# LPCB235_-_HEC1-4.net
KiCad netlist of a schematic drawn in Altium Designer
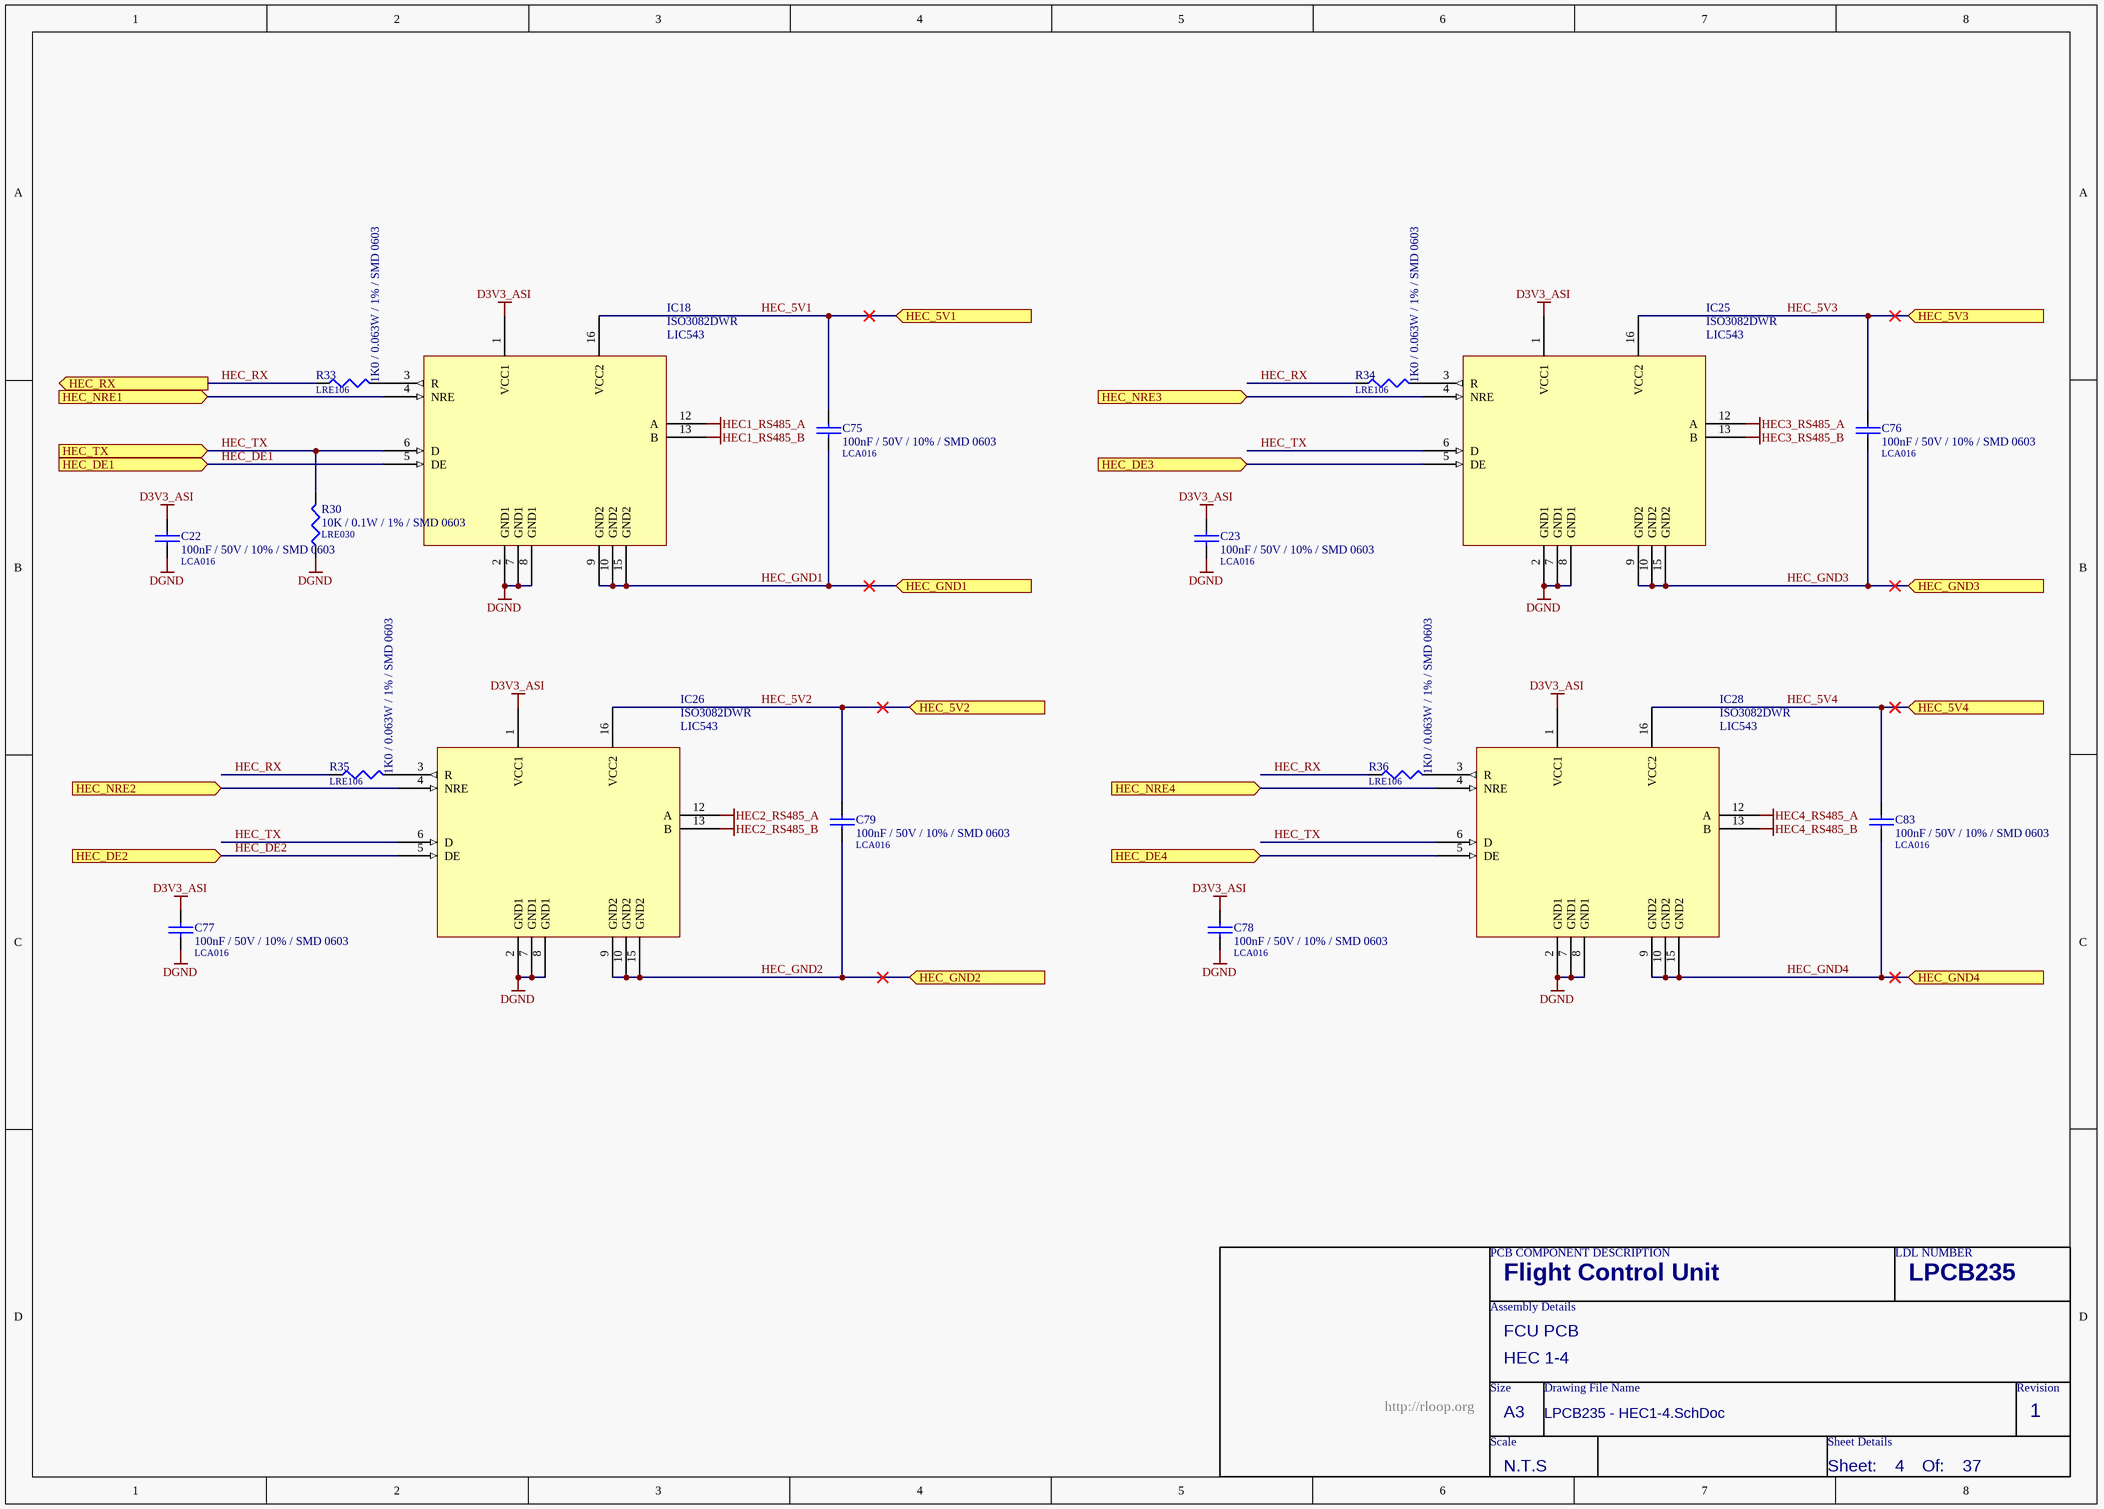
[diagram p0: LPCB235 - HEC1-4.SchDoc]

(export (version "E")
  (design (tool "Eeschema 10.0.6"))
  (components
    (comp (ref "C22")
      (value "100nF / 50V / 10% / SMD 0603")
      (footprint "LFP011__CC1608-0603-IPC7351_B")
      (description "Capacitor, Ceramic Chip, 100nF (0.1uF), 50V, 5%, SMD 0603 [LCA016]")
      (fields (field (name "LDL_NUMBER") "LCA016"))
      (libsource (lib "LDL_Capacitors") (part "100nF / 50V / 10% / SMD 0603"))
    )
    (comp (ref "C23")
      (value "100nF / 50V / 10% / SMD 0603")
      (footprint "LFP011__CC1608-0603-IPC7351_B")
      (description "Capacitor, Ceramic Chip, 100nF (0.1uF), 50V, 5%, SMD 0603 [LCA016]")
      (fields (field (name "LDL_NUMBER") "LCA016"))
      (libsource (lib "LDL_Capacitors") (part "100nF / 50V / 10% / SMD 0603"))
    )
    (comp (ref "C75")
      (value "100nF / 50V / 10% / SMD 0603")
      (footprint "LFP011__CC1608-0603-IPC7351_B")
      (description "Capacitor, Ceramic Chip, 100nF (0.1uF), 50V, 5%, SMD 0603 [LCA016]")
      (fields (field (name "LDL_NUMBER") "LCA016"))
      (libsource (lib "LDL_Capacitors") (part "100nF / 50V / 10% / SMD 0603"))
    )
    (comp (ref "C76")
      (value "100nF / 50V / 10% / SMD 0603")
      (footprint "LFP011__CC1608-0603-IPC7351_B")
      (description "Capacitor, Ceramic Chip, 100nF (0.1uF), 50V, 5%, SMD 0603 [LCA016]")
      (fields (field (name "LDL_NUMBER") "LCA016"))
      (libsource (lib "LDL_Capacitors") (part "100nF / 50V / 10% / SMD 0603"))
    )
    (comp (ref "C77")
      (value "100nF / 50V / 10% / SMD 0603")
      (footprint "LFP011__CC1608-0603-IPC7351_B")
      (description "Capacitor, Ceramic Chip, 100nF (0.1uF), 50V, 5%, SMD 0603 [LCA016]")
      (fields (field (name "LDL_NUMBER") "LCA016"))
      (libsource (lib "LDL_Capacitors") (part "100nF / 50V / 10% / SMD 0603"))
    )
    (comp (ref "C78")
      (value "100nF / 50V / 10% / SMD 0603")
      (footprint "LFP011__CC1608-0603-IPC7351_B")
      (description "Capacitor, Ceramic Chip, 100nF (0.1uF), 50V, 5%, SMD 0603 [LCA016]")
      (fields (field (name "LDL_NUMBER") "LCA016"))
      (libsource (lib "LDL_Capacitors") (part "100nF / 50V / 10% / SMD 0603"))
    )
    (comp (ref "C79")
      (value "100nF / 50V / 10% / SMD 0603")
      (footprint "LFP011__CC1608-0603-IPC7351_B")
      (description "Capacitor, Ceramic Chip, 100nF (0.1uF), 50V, 5%, SMD 0603 [LCA016]")
      (fields (field (name "LDL_NUMBER") "LCA016"))
      (libsource (lib "LDL_Capacitors") (part "100nF / 50V / 10% / SMD 0603"))
    )
    (comp (ref "C83")
      (value "100nF / 50V / 10% / SMD 0603")
      (footprint "LFP011__CC1608-0603-IPC7351_B")
      (description "Capacitor, Ceramic Chip, 100nF (0.1uF), 50V, 5%, SMD 0603 [LCA016]")
      (fields (field (name "LDL_NUMBER") "LCA016"))
      (libsource (lib "LDL_Capacitors") (part "100nF / 50V / 10% / SMD 0603"))
    )
    (comp (ref "IC18")
      (value "ISO3082DWR")
      (footprint "LFP068__SO-G16/G6.9")
      (description "IC, RS485 Isolator, SMD SOIC 16 [LIC543]")
      (fields (field (name "LDL_NUMBER") "LIC543"))
      (libsource (lib "LDL_Semiconductors") (part "ISO3082DWR"))
    )
    (comp (ref "IC25")
      (value "ISO3082DWR")
      (footprint "LFP068__SO-G16/G6.9")
      (description "IC, RS485 Isolator, SMD SOIC 16 [LIC543]")
      (fields (field (name "LDL_NUMBER") "LIC543"))
      (libsource (lib "LDL_Semiconductors") (part "ISO3082DWR"))
    )
    (comp (ref "IC26")
      (value "ISO3082DWR")
      (footprint "LFP068__SO-G16/G6.9")
      (description "IC, RS485 Isolator, SMD SOIC 16 [LIC543]")
      (fields (field (name "LDL_NUMBER") "LIC543"))
      (libsource (lib "LDL_Semiconductors") (part "ISO3082DWR"))
    )
    (comp (ref "IC28")
      (value "ISO3082DWR")
      (footprint "LFP068__SO-G16/G6.9")
      (description "IC, RS485 Isolator, SMD SOIC 16 [LIC543]")
      (fields (field (name "LDL_NUMBER") "LIC543"))
      (libsource (lib "LDL_Semiconductors") (part "ISO3082DWR"))
    )
    (comp (ref "R30")
      (value "10K / 0.1W / 1% / SMD 0603")
      (footprint "LFP020__CR1608-0603-IPC7351_B")
      (description "Resistor, Ceramic Chip, 10K, 0.1W, 1%, SMD 0603 [LRE030]")
      (fields (field (name "LDL_NUMBER") "LRE030"))
      (libsource (lib "LDL_Resistors") (part "10K / 0.1W / 1% / SMD 0603"))
    )
    (comp (ref "R33")
      (value "1K0 / 0.063W / 1% / SMD 0603")
      (footprint "LFP020__CR1608-0603-IPC7351_B")
      (description "Resistor, Ceramic Chip, 1K0, 0.063W, 1%, SMD 0603 [LRE106]")
      (fields (field (name "LDL_NUMBER") "LRE106"))
      (libsource (lib "LDL_Resistors") (part "1K0 / 0.063W / 1% / SMD 0603"))
    )
    (comp (ref "R34")
      (value "1K0 / 0.063W / 1% / SMD 0603")
      (footprint "LFP020__CR1608-0603-IPC7351_B")
      (description "Resistor, Ceramic Chip, 1K0, 0.063W, 1%, SMD 0603 [LRE106]")
      (fields (field (name "LDL_NUMBER") "LRE106"))
      (libsource (lib "LDL_Resistors") (part "1K0 / 0.063W / 1% / SMD 0603"))
    )
    (comp (ref "R35")
      (value "1K0 / 0.063W / 1% / SMD 0603")
      (footprint "LFP020__CR1608-0603-IPC7351_B")
      (description "Resistor, Ceramic Chip, 1K0, 0.063W, 1%, SMD 0603 [LRE106]")
      (fields (field (name "LDL_NUMBER") "LRE106"))
      (libsource (lib "LDL_Resistors") (part "1K0 / 0.063W / 1% / SMD 0603"))
    )
    (comp (ref "R36")
      (value "1K0 / 0.063W / 1% / SMD 0603")
      (footprint "LFP020__CR1608-0603-IPC7351_B")
      (description "Resistor, Ceramic Chip, 1K0, 0.063W, 1%, SMD 0603 [LRE106]")
      (fields (field (name "LDL_NUMBER") "LRE106"))
      (libsource (lib "LDL_Resistors") (part "1K0 / 0.063W / 1% / SMD 0603"))
    )
  )
  (nets
    (net (code "1") (name "/HEC_5V1") (class "Default")
      (node (ref "C75") (pin "1") (pintype "passive"))
      (node (ref "IC18") (pin "16") (pinfunction "VCC2_16") (pintype "power_in"))
    )
    (net (code "2") (name "/HEC_5V2") (class "Default")
      (node (ref "C79") (pin "1") (pintype "passive"))
      (node (ref "IC26") (pin "16") (pinfunction "VCC2_16") (pintype "power_in"))
    )
    (net (code "3") (name "/HEC_5V3") (class "Default")
      (node (ref "C76") (pin "1") (pintype "passive"))
      (node (ref "IC25") (pin "16") (pinfunction "VCC2_16") (pintype "power_in"))
    )
    (net (code "4") (name "/HEC_5V4") (class "Default")
      (node (ref "C83") (pin "1") (pintype "passive"))
      (node (ref "IC28") (pin "16") (pinfunction "VCC2_16") (pintype "power_in"))
    )
    (net (code "5") (name "/HEC_DE1") (class "Default")
      (node (ref "IC18") (pin "5") (pinfunction "DE_5") (pintype "input"))
    )
    (net (code "6") (name "/HEC_DE2") (class "Default")
      (node (ref "IC26") (pin "5") (pinfunction "DE_5") (pintype "input"))
    )
    (net (code "7") (name "/HEC_DE3") (class "Default")
      (node (ref "IC25") (pin "5") (pinfunction "DE_5") (pintype "input"))
    )
    (net (code "8") (name "/HEC_DE4") (class "Default")
      (node (ref "IC28") (pin "5") (pinfunction "DE_5") (pintype "input"))
    )
    (net (code "9") (name "/HEC_GND1") (class "Default")
      (node (ref "C75") (pin "2") (pintype "passive"))
      (node (ref "IC18") (pin "10") (pinfunction "GND2_10") (pintype "power_in"))
      (node (ref "IC18") (pin "15") (pinfunction "GND2_15") (pintype "power_in"))
      (node (ref "IC18") (pin "9") (pinfunction "GND2_9") (pintype "power_in"))
    )
    (net (code "10") (name "/HEC_GND2") (class "Default")
      (node (ref "C79") (pin "2") (pintype "passive"))
      (node (ref "IC26") (pin "10") (pinfunction "GND2_10") (pintype "power_in"))
      (node (ref "IC26") (pin "15") (pinfunction "GND2_15") (pintype "power_in"))
      (node (ref "IC26") (pin "9") (pinfunction "GND2_9") (pintype "power_in"))
    )
    (net (code "11") (name "/HEC_GND3") (class "Default")
      (node (ref "C76") (pin "2") (pintype "passive"))
      (node (ref "IC25") (pin "10") (pinfunction "GND2_10") (pintype "power_in"))
      (node (ref "IC25") (pin "15") (pinfunction "GND2_15") (pintype "power_in"))
      (node (ref "IC25") (pin "9") (pinfunction "GND2_9") (pintype "power_in"))
    )
    (net (code "12") (name "/HEC_GND4") (class "Default")
      (node (ref "C83") (pin "2") (pintype "passive"))
      (node (ref "IC28") (pin "10") (pinfunction "GND2_10") (pintype "power_in"))
      (node (ref "IC28") (pin "15") (pinfunction "GND2_15") (pintype "power_in"))
      (node (ref "IC28") (pin "9") (pinfunction "GND2_9") (pintype "power_in"))
    )
    (net (code "13") (name "/HEC_NRE1") (class "Default")
      (node (ref "IC18") (pin "4") (pinfunction "NRE_4") (pintype "input"))
    )
    (net (code "14") (name "/HEC_NRE2") (class "Default")
      (node (ref "IC26") (pin "4") (pinfunction "NRE_4") (pintype "input"))
    )
    (net (code "15") (name "/HEC_NRE3") (class "Default")
      (node (ref "IC25") (pin "4") (pinfunction "NRE_4") (pintype "input"))
    )
    (net (code "16") (name "/HEC_NRE4") (class "Default")
      (node (ref "IC28") (pin "4") (pinfunction "NRE_4") (pintype "input"))
    )
    (net (code "17") (name "/HEC_RX") (class "Default")
      (node (ref "R33") (pin "1") (pintype "passive"))
      (node (ref "R34") (pin "1") (pintype "passive"))
      (node (ref "R35") (pin "1") (pintype "passive"))
      (node (ref "R36") (pin "1") (pintype "passive"))
    )
    (net (code "18") (name "/HEC_TX") (class "Default")
      (node (ref "IC18") (pin "6") (pinfunction "D_6") (pintype "input"))
      (node (ref "IC25") (pin "6") (pinfunction "D_6") (pintype "input"))
      (node (ref "IC26") (pin "6") (pinfunction "D_6") (pintype "input"))
      (node (ref "IC28") (pin "6") (pinfunction "D_6") (pintype "input"))
      (node (ref "R30") (pin "2") (pintype "passive"))
    )
    (net (code "19") (name "D3V3_ASI") (class "Default")
      (node (ref "C22") (pin "1") (pintype "passive"))
      (node (ref "C23") (pin "1") (pintype "passive"))
      (node (ref "C77") (pin "1") (pintype "passive"))
      (node (ref "C78") (pin "1") (pintype "passive"))
      (node (ref "IC18") (pin "1") (pinfunction "VCC1_1") (pintype "power_in"))
      (node (ref "IC25") (pin "1") (pinfunction "VCC1_1") (pintype "power_in"))
      (node (ref "IC26") (pin "1") (pinfunction "VCC1_1") (pintype "power_in"))
      (node (ref "IC28") (pin "1") (pinfunction "VCC1_1") (pintype "power_in"))
    )
    (net (code "20") (name "DGND") (class "Default")
      (node (ref "C22") (pin "2") (pintype "passive"))
      (node (ref "C23") (pin "2") (pintype "passive"))
      (node (ref "C77") (pin "2") (pintype "passive"))
      (node (ref "C78") (pin "2") (pintype "passive"))
      (node (ref "IC18") (pin "2") (pinfunction "GND1_2") (pintype "power_in"))
      (node (ref "IC18") (pin "7") (pinfunction "GND1_7") (pintype "power_in"))
      (node (ref "IC18") (pin "8") (pinfunction "GND1_8") (pintype "power_in"))
      (node (ref "IC25") (pin "2") (pinfunction "GND1_2") (pintype "power_in"))
      (node (ref "IC25") (pin "7") (pinfunction "GND1_7") (pintype "power_in"))
      (node (ref "IC25") (pin "8") (pinfunction "GND1_8") (pintype "power_in"))
      (node (ref "IC26") (pin "2") (pinfunction "GND1_2") (pintype "power_in"))
      (node (ref "IC26") (pin "7") (pinfunction "GND1_7") (pintype "power_in"))
      (node (ref "IC26") (pin "8") (pinfunction "GND1_8") (pintype "power_in"))
      (node (ref "IC28") (pin "2") (pinfunction "GND1_2") (pintype "power_in"))
      (node (ref "IC28") (pin "7") (pinfunction "GND1_7") (pintype "power_in"))
      (node (ref "IC28") (pin "8") (pinfunction "GND1_8") (pintype "power_in"))
      (node (ref "R30") (pin "1") (pintype "passive"))
    )
    (net (code "21") (name "HEC1_RS485_A") (class "Default")
      (node (ref "IC18") (pin "12") (pinfunction "A_12") (pintype "passive"))
    )
    (net (code "22") (name "HEC1_RS485_B") (class "Default")
      (node (ref "IC18") (pin "13") (pinfunction "B_13") (pintype "passive"))
    )
    (net (code "23") (name "HEC2_RS485_A") (class "Default")
      (node (ref "IC26") (pin "12") (pinfunction "A_12") (pintype "passive"))
    )
    (net (code "24") (name "HEC2_RS485_B") (class "Default")
      (node (ref "IC26") (pin "13") (pinfunction "B_13") (pintype "passive"))
    )
    (net (code "25") (name "HEC3_RS485_A") (class "Default")
      (node (ref "IC25") (pin "12") (pinfunction "A_12") (pintype "passive"))
    )
    (net (code "26") (name "HEC3_RS485_B") (class "Default")
      (node (ref "IC25") (pin "13") (pinfunction "B_13") (pintype "passive"))
    )
    (net (code "27") (name "HEC4_RS485_A") (class "Default")
      (node (ref "IC28") (pin "12") (pinfunction "A_12") (pintype "passive"))
    )
    (net (code "28") (name "HEC4_RS485_B") (class "Default")
      (node (ref "IC28") (pin "13") (pinfunction "B_13") (pintype "passive"))
    )
    (net (code "29") (name "Net-(IC18-R)") (class "Default")
      (node (ref "IC18") (pin "3") (pinfunction "R_3") (pintype "output"))
      (node (ref "R33") (pin "2") (pintype "passive"))
    )
    (net (code "30") (name "Net-(IC25-R)") (class "Default")
      (node (ref "IC25") (pin "3") (pinfunction "R_3") (pintype "output"))
      (node (ref "R34") (pin "2") (pintype "passive"))
    )
    (net (code "31") (name "Net-(IC26-R)") (class "Default")
      (node (ref "IC26") (pin "3") (pinfunction "R_3") (pintype "output"))
      (node (ref "R35") (pin "2") (pintype "passive"))
    )
    (net (code "32") (name "Net-(IC28-R)") (class "Default")
      (node (ref "IC28") (pin "3") (pinfunction "R_3") (pintype "output"))
      (node (ref "R36") (pin "2") (pintype "passive"))
    )
  )
)
